# External_Supply_Interface.net
KiCad netlist of a schematic drawn in Altium Designer
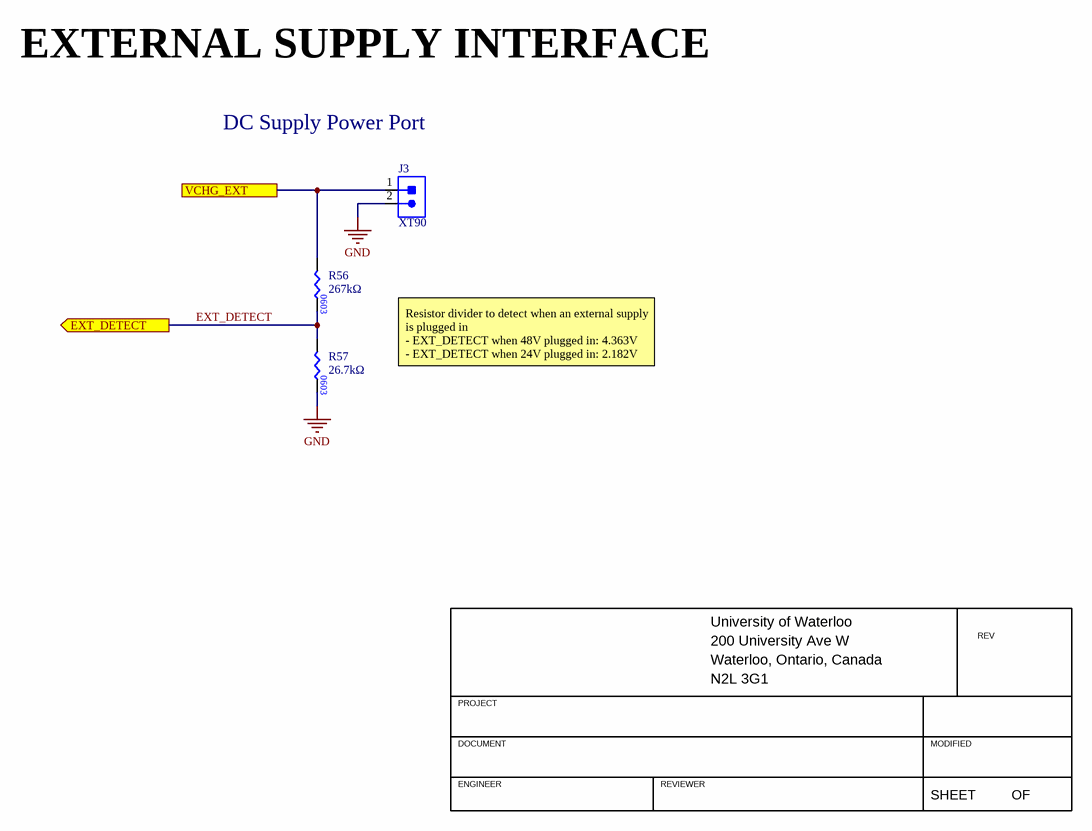
[diagram p0: External Supply Interface.SchDoc]

(export (version "E")
  (design (tool "Eeschema 10.0.6"))
  (components
    (comp (ref "J3")
      (value "CON_2POS_XT90")
      (footprint "XT90")
      (description "HIGH QUALITY GOLD PLATED XT90 MA")
      (fields (field (name "PACKAGE/FOOTPRINT") "XT90"))
      (libsource (lib "Personal_Schematic_Library_2022") (part "CON_2POS_XT90"))
    )
    (comp (ref "R56")
      (value "267kΩ")
      (footprint "RES0603")
      (description "RES 267K OHM 1% 1/10W 0603")
      (fields (field (name "Comment") "RES_267kΩ_0603_1%"))
      (libsource (lib "Personal_Schematic_Library_2022") (part "RES_267kΩ_0603_1%"))
    )
    (comp (ref "R57")
      (value "26.7kΩ")
      (footprint "RES0603")
      (description "RES 26.7K OHM 1% 1/10W 0603")
      (fields (field (name "Comment") "RES_26.7kΩ_0603_1%"))
      (libsource (lib "Personal_Schematic_Library_2022") (part "RES_26.7kΩ_0603_1%"))
    )
  )
  (nets
    (net (code "1") (name "/EXT_DETECT") (class "Default")
      (node (ref "R56") (pin "2") (pinfunction "2_2") (pintype "passive"))
      (node (ref "R57") (pin "1") (pinfunction "1_1") (pintype "passive"))
    )
    (net (code "2") (name "/VCHG_EXT") (class "Default")
      (node (ref "J3") (pin "1") (pinfunction "1_1") (pintype "passive"))
      (node (ref "R56") (pin "1") (pinfunction "1_1") (pintype "passive"))
    )
    (net (code "3") (name "GND") (class "Default")
      (node (ref "J3") (pin "2") (pinfunction "2_2") (pintype "passive"))
      (node (ref "R57") (pin "2") (pinfunction "2_2") (pintype "passive"))
    )
  )
)
